# itrope-serial-v01.net
KiCad netlist of a schematic drawn in EAGLE
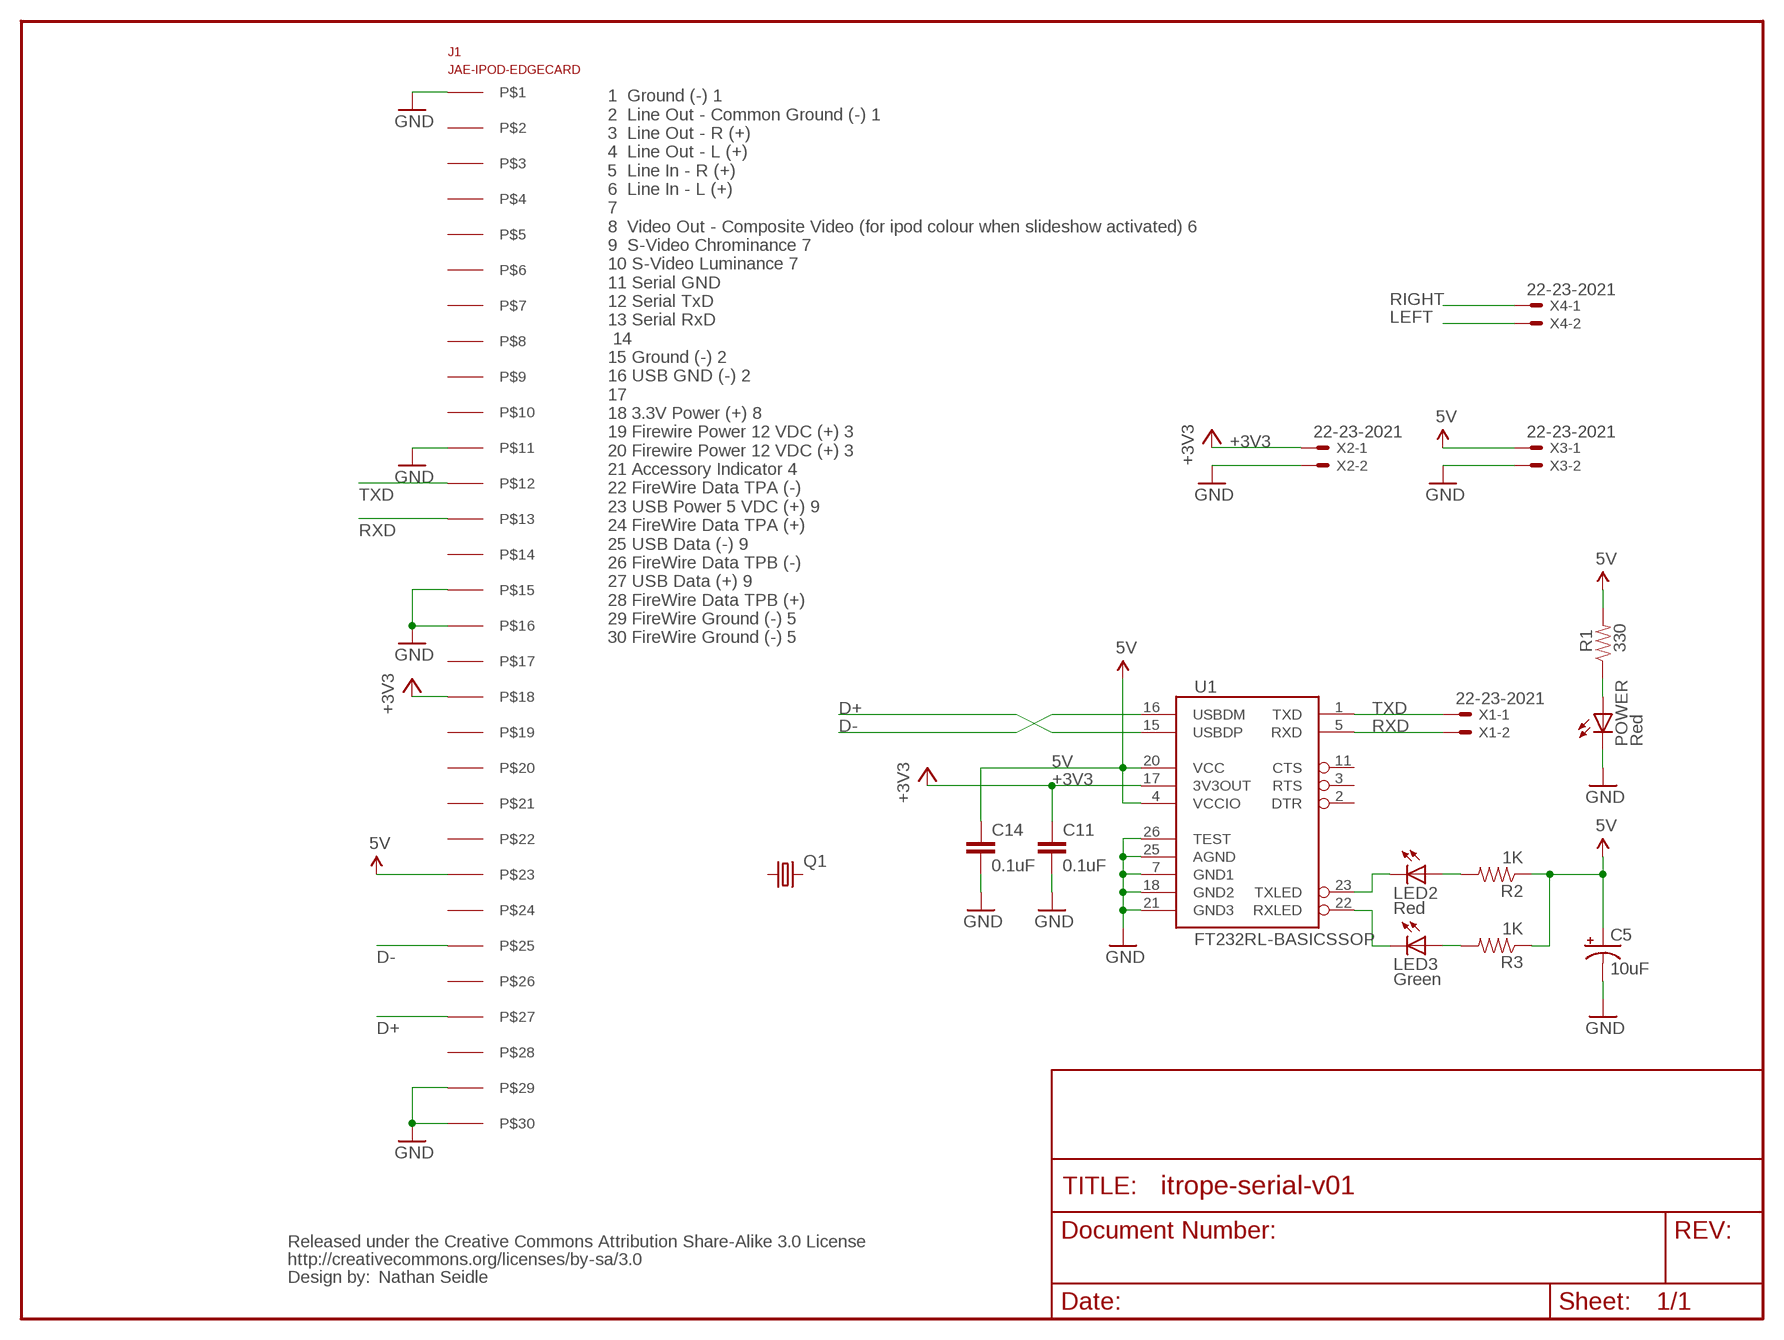
[diagram p0: schematic, sheet 1]

(export (version "E")
  (design (tool "Eeschema 10.0.6"))
  (components
    (comp (ref "C5")
      (value "10uF")
      (footprint "eagle-import:EIA3216")
      (libsource (lib "eagle-import") (part "CAP_POL1206"))
    )
    (comp (ref "C11")
      (value "0.1uF")
      (footprint "eagle-import:C0402")
      (libsource (lib "eagle-import") (part "CAP0402"))
    )
    (comp (ref "C14")
      (value "0.1uF")
      (footprint "eagle-import:C0402")
      (libsource (lib "eagle-import") (part "CAP0402"))
    )
    (comp (ref "J1")
      (value "JAE-IPOD-EDGECARD")
      (footprint "eagle-import:30PINEDGE")
      (libsource (lib "eagle-import") (part "JAE-IPOD-EDGECARD"))
    )
    (comp (ref "LED2")
      (value "Red")
      (footprint "eagle-import:LED-0603")
      (libsource (lib "eagle-import") (part "LED0603"))
    )
    (comp (ref "LED3")
      (value "Green")
      (footprint "eagle-import:LED-0603")
      (libsource (lib "eagle-import") (part "LED0603"))
    )
    (comp (ref "POWER")
      (value "Red")
      (footprint "eagle-import:LED-0603")
      (libsource (lib "eagle-import") (part "LED0603"))
    )
    (comp (ref "Q1")
      (value "CRYSTALSM49")
      (footprint "eagle-import:SM49")
      (libsource (lib "eagle-import") (part "CRYSTALSM49"))
    )
    (comp (ref "R1")
      (value "330")
      (footprint "eagle-import:C0402")
      (libsource (lib "eagle-import") (part "RESISTOR0402"))
    )
    (comp (ref "R2")
      (value "1K")
      (footprint "eagle-import:C0402")
      (libsource (lib "eagle-import") (part "RESISTOR0402"))
    )
    (comp (ref "R3")
      (value "1K")
      (footprint "eagle-import:C0402")
      (libsource (lib "eagle-import") (part "RESISTOR0402"))
    )
    (comp (ref "U$9")
      (value "CREATIVE_COMMONS")
      (footprint "eagle-import:CREATIVE_COMMONS")
      (libsource (lib "eagle-import") (part "CREATIVE_COMMONS"))
    )
    (comp (ref "U1")
      (value "FT232RL-BASICSSOP")
      (footprint "eagle-import:SSOP28DB")
      (libsource (lib "eagle-import") (part "FT232RL-BASICSSOP"))
    )
    (comp (ref "X1")
      (value "22-23-2021")
      (footprint "eagle-import:22-23-2021")
      (fields (field (name "MF") "MOLEX"))
      (libsource (lib "eagle-import") (part "22-23-2021"))
    )
    (comp (ref "X2")
      (value "22-23-2021")
      (footprint "eagle-import:22-23-2021")
      (fields (field (name "MF") "MOLEX"))
      (libsource (lib "eagle-import") (part "22-23-2021"))
    )
    (comp (ref "X3")
      (value "22-23-2021")
      (footprint "eagle-import:22-23-2021")
      (fields (field (name "MF") "MOLEX"))
      (libsource (lib "eagle-import") (part "22-23-2021"))
    )
    (comp (ref "X4")
      (value "22-23-2021")
      (footprint "eagle-import:22-23-2021")
      (fields (field (name "MF") "MOLEX"))
      (libsource (lib "eagle-import") (part "22-23-2021"))
    )
  )
  (nets
    (net (code "1") (name "+3V3") (class "Default")
      (node (ref "C11") (pin "1") (pinfunction "1_1") (pintype "passive"))
      (node (ref "J1") (pin "P$18") (pinfunction "P$18_P$18") (pintype "bidirectional"))
      (node (ref "U1") (pin "17") (pinfunction "3V3OUT_17") (pintype "output"))
      (node (ref "X2") (pin "1") (pinfunction "S_1") (pintype "passive"))
    )
    (net (code "2") (name "/D+") (class "Default")
      (node (ref "J1") (pin "P$27") (pinfunction "P$27_P$27") (pintype "bidirectional"))
      (node (ref "U1") (pin "15") (pinfunction "USBDP_15") (pintype "bidirectional"))
    )
    (net (code "3") (name "/D-") (class "Default")
      (node (ref "J1") (pin "P$25") (pinfunction "P$25_P$25") (pintype "bidirectional"))
      (node (ref "U1") (pin "16") (pinfunction "USBDM_16") (pintype "bidirectional"))
    )
    (net (code "4") (name "/LEFT") (class "Default")
      (node (ref "X4") (pin "2") (pinfunction "S_2") (pintype "passive"))
    )
    (net (code "5") (name "/RIGHT") (class "Default")
      (node (ref "X4") (pin "1") (pinfunction "S_1") (pintype "passive"))
    )
    (net (code "6") (name "/RXD") (class "Default")
      (node (ref "J1") (pin "P$13") (pinfunction "P$13_P$13") (pintype "bidirectional"))
      (node (ref "U1") (pin "5") (pinfunction "RXD_5") (pintype "input"))
      (node (ref "X1") (pin "2") (pinfunction "S_2") (pintype "passive"))
    )
    (net (code "7") (name "/TXD") (class "Default")
      (node (ref "J1") (pin "P$12") (pinfunction "P$12_P$12") (pintype "bidirectional"))
      (node (ref "U1") (pin "1") (pinfunction "TXD_1") (pintype "output"))
      (node (ref "X1") (pin "1") (pinfunction "S_1") (pintype "passive"))
    )
    (net (code "8") (name "5V") (class "Default")
      (node (ref "C14") (pin "1") (pinfunction "1_1") (pintype "passive"))
      (node (ref "C5") (pin "A") (pinfunction "+_A") (pintype "passive"))
      (node (ref "J1") (pin "P$23") (pinfunction "P$23_P$23") (pintype "bidirectional"))
      (node (ref "R1") (pin "2") (pinfunction "2_2") (pintype "passive"))
      (node (ref "R2") (pin "1") (pinfunction "1_1") (pintype "passive"))
      (node (ref "R3") (pin "1") (pinfunction "1_1") (pintype "passive"))
      (node (ref "U1") (pin "20") (pinfunction "VCC_20") (pintype "power_in"))
      (node (ref "U1") (pin "4") (pinfunction "VCCIO_4") (pintype "power_in"))
      (node (ref "X3") (pin "1") (pinfunction "S_1") (pintype "passive"))
    )
    (net (code "9") (name "GND") (class "Default")
      (node (ref "C11") (pin "2") (pinfunction "2_2") (pintype "passive"))
      (node (ref "C14") (pin "2") (pinfunction "2_2") (pintype "passive"))
      (node (ref "C5") (pin "C") (pinfunction "-_C") (pintype "passive"))
      (node (ref "J1") (pin "P$1") (pinfunction "P$1_P$1") (pintype "bidirectional"))
      (node (ref "J1") (pin "P$11") (pinfunction "P$11_P$11") (pintype "bidirectional"))
      (node (ref "J1") (pin "P$15") (pinfunction "P$15_P$15") (pintype "bidirectional"))
      (node (ref "J1") (pin "P$16") (pinfunction "P$16_P$16") (pintype "bidirectional"))
      (node (ref "J1") (pin "P$29") (pinfunction "P$29_P$29") (pintype "bidirectional"))
      (node (ref "J1") (pin "P$30") (pinfunction "P$30_P$30") (pintype "bidirectional"))
      (node (ref "POWER") (pin "C") (pinfunction "C_C") (pintype "passive"))
      (node (ref "U1") (pin "18") (pinfunction "GND2_18") (pintype "power_in"))
      (node (ref "U1") (pin "21") (pinfunction "GND3_21") (pintype "power_in"))
      (node (ref "U1") (pin "25") (pinfunction "AGND_25") (pintype "power_in"))
      (node (ref "U1") (pin "26") (pinfunction "TEST_26") (pintype "input"))
      (node (ref "U1") (pin "7") (pinfunction "GND1_7") (pintype "power_in"))
      (node (ref "X2") (pin "2") (pinfunction "S_2") (pintype "passive"))
      (node (ref "X3") (pin "2") (pinfunction "S_2") (pintype "passive"))
    )
    (net (code "10") (name "Net-(LED2-PadA)") (class "Default")
      (node (ref "LED2") (pin "A") (pinfunction "A_A") (pintype "passive"))
      (node (ref "R2") (pin "2") (pinfunction "2_2") (pintype "passive"))
    )
    (net (code "11") (name "Net-(LED3-PadA)") (class "Default")
      (node (ref "LED3") (pin "A") (pinfunction "A_A") (pintype "passive"))
      (node (ref "R3") (pin "2") (pinfunction "2_2") (pintype "passive"))
    )
    (net (code "12") (name "Net-(POWER-PadA)") (class "Default")
      (node (ref "POWER") (pin "A") (pinfunction "A_A") (pintype "passive"))
      (node (ref "R1") (pin "1") (pinfunction "1_1") (pintype "passive"))
    )
    (net (code "13") (name "Net-(U1-RXLED)") (class "Default")
      (node (ref "LED3") (pin "C") (pinfunction "C_C") (pintype "passive"))
      (node (ref "U1") (pin "22") (pinfunction "RXLED_22") (pintype "bidirectional"))
    )
    (net (code "14") (name "Net-(U1-TXLED)") (class "Default")
      (node (ref "LED2") (pin "C") (pinfunction "C_C") (pintype "passive"))
      (node (ref "U1") (pin "23") (pinfunction "TXLED_23") (pintype "bidirectional"))
    )
    (net (code "15") (name "unconnected-(J1-PadP$2)") (class "Default")
      (node (ref "J1") (pin "P$2") (pinfunction "P$2_P$2") (pintype "bidirectional"))
    )
    (net (code "16") (name "unconnected-(J1-PadP$3)") (class "Default")
      (node (ref "J1") (pin "P$3") (pinfunction "P$3_P$3") (pintype "bidirectional"))
    )
    (net (code "17") (name "unconnected-(J1-PadP$4)") (class "Default")
      (node (ref "J1") (pin "P$4") (pinfunction "P$4_P$4") (pintype "bidirectional"))
    )
    (net (code "18") (name "unconnected-(J1-PadP$5)") (class "Default")
      (node (ref "J1") (pin "P$5") (pinfunction "P$5_P$5") (pintype "bidirectional"))
    )
    (net (code "19") (name "unconnected-(J1-PadP$6)") (class "Default")
      (node (ref "J1") (pin "P$6") (pinfunction "P$6_P$6") (pintype "bidirectional"))
    )
    (net (code "20") (name "unconnected-(J1-PadP$7)") (class "Default")
      (node (ref "J1") (pin "P$7") (pinfunction "P$7_P$7") (pintype "bidirectional"))
    )
    (net (code "21") (name "unconnected-(J1-PadP$8)") (class "Default")
      (node (ref "J1") (pin "P$8") (pinfunction "P$8_P$8") (pintype "bidirectional"))
    )
    (net (code "22") (name "unconnected-(J1-PadP$9)") (class "Default")
      (node (ref "J1") (pin "P$9") (pinfunction "P$9_P$9") (pintype "bidirectional"))
    )
    (net (code "23") (name "unconnected-(J1-PadP$10)") (class "Default")
      (node (ref "J1") (pin "P$10") (pinfunction "P$10_P$10") (pintype "bidirectional"))
    )
    (net (code "24") (name "unconnected-(J1-PadP$14)") (class "Default")
      (node (ref "J1") (pin "P$14") (pinfunction "P$14_P$14") (pintype "bidirectional"))
    )
    (net (code "25") (name "unconnected-(J1-PadP$17)") (class "Default")
      (node (ref "J1") (pin "P$17") (pinfunction "P$17_P$17") (pintype "bidirectional"))
    )
    (net (code "26") (name "unconnected-(J1-PadP$19)") (class "Default")
      (node (ref "J1") (pin "P$19") (pinfunction "P$19_P$19") (pintype "bidirectional"))
    )
    (net (code "27") (name "unconnected-(J1-PadP$20)") (class "Default")
      (node (ref "J1") (pin "P$20") (pinfunction "P$20_P$20") (pintype "bidirectional"))
    )
    (net (code "28") (name "unconnected-(J1-PadP$21)") (class "Default")
      (node (ref "J1") (pin "P$21") (pinfunction "P$21_P$21") (pintype "bidirectional"))
    )
    (net (code "29") (name "unconnected-(J1-PadP$22)") (class "Default")
      (node (ref "J1") (pin "P$22") (pinfunction "P$22_P$22") (pintype "bidirectional"))
    )
    (net (code "30") (name "unconnected-(J1-PadP$24)") (class "Default")
      (node (ref "J1") (pin "P$24") (pinfunction "P$24_P$24") (pintype "bidirectional"))
    )
    (net (code "31") (name "unconnected-(J1-PadP$26)") (class "Default")
      (node (ref "J1") (pin "P$26") (pinfunction "P$26_P$26") (pintype "bidirectional"))
    )
    (net (code "32") (name "unconnected-(J1-PadP$28)") (class "Default")
      (node (ref "J1") (pin "P$28") (pinfunction "P$28_P$28") (pintype "bidirectional"))
    )
    (net (code "33") (name "unconnected-(Q1-Pad1)") (class "Default")
      (node (ref "Q1") (pin "1") (pinfunction "1_1") (pintype "passive"))
    )
    (net (code "34") (name "unconnected-(Q1-Pad2)") (class "Default")
      (node (ref "Q1") (pin "2") (pinfunction "2_2") (pintype "passive"))
    )
    (net (code "35") (name "unconnected-(U1-CTS-Pad11)") (class "Default")
      (node (ref "U1") (pin "11") (pinfunction "CTS_11") (pintype "bidirectional"))
    )
    (net (code "36") (name "unconnected-(U1-DTR-Pad2)") (class "Default")
      (node (ref "U1") (pin "2") (pinfunction "DTR_2") (pintype "bidirectional"))
    )
    (net (code "37") (name "unconnected-(U1-RTS-Pad3)") (class "Default")
      (node (ref "U1") (pin "3") (pinfunction "RTS_3") (pintype "bidirectional"))
    )
  )
)
